# HHKBLite2BTforArduinoProMicro33.net
KiCad netlist of a schematic drawn in EAGLE
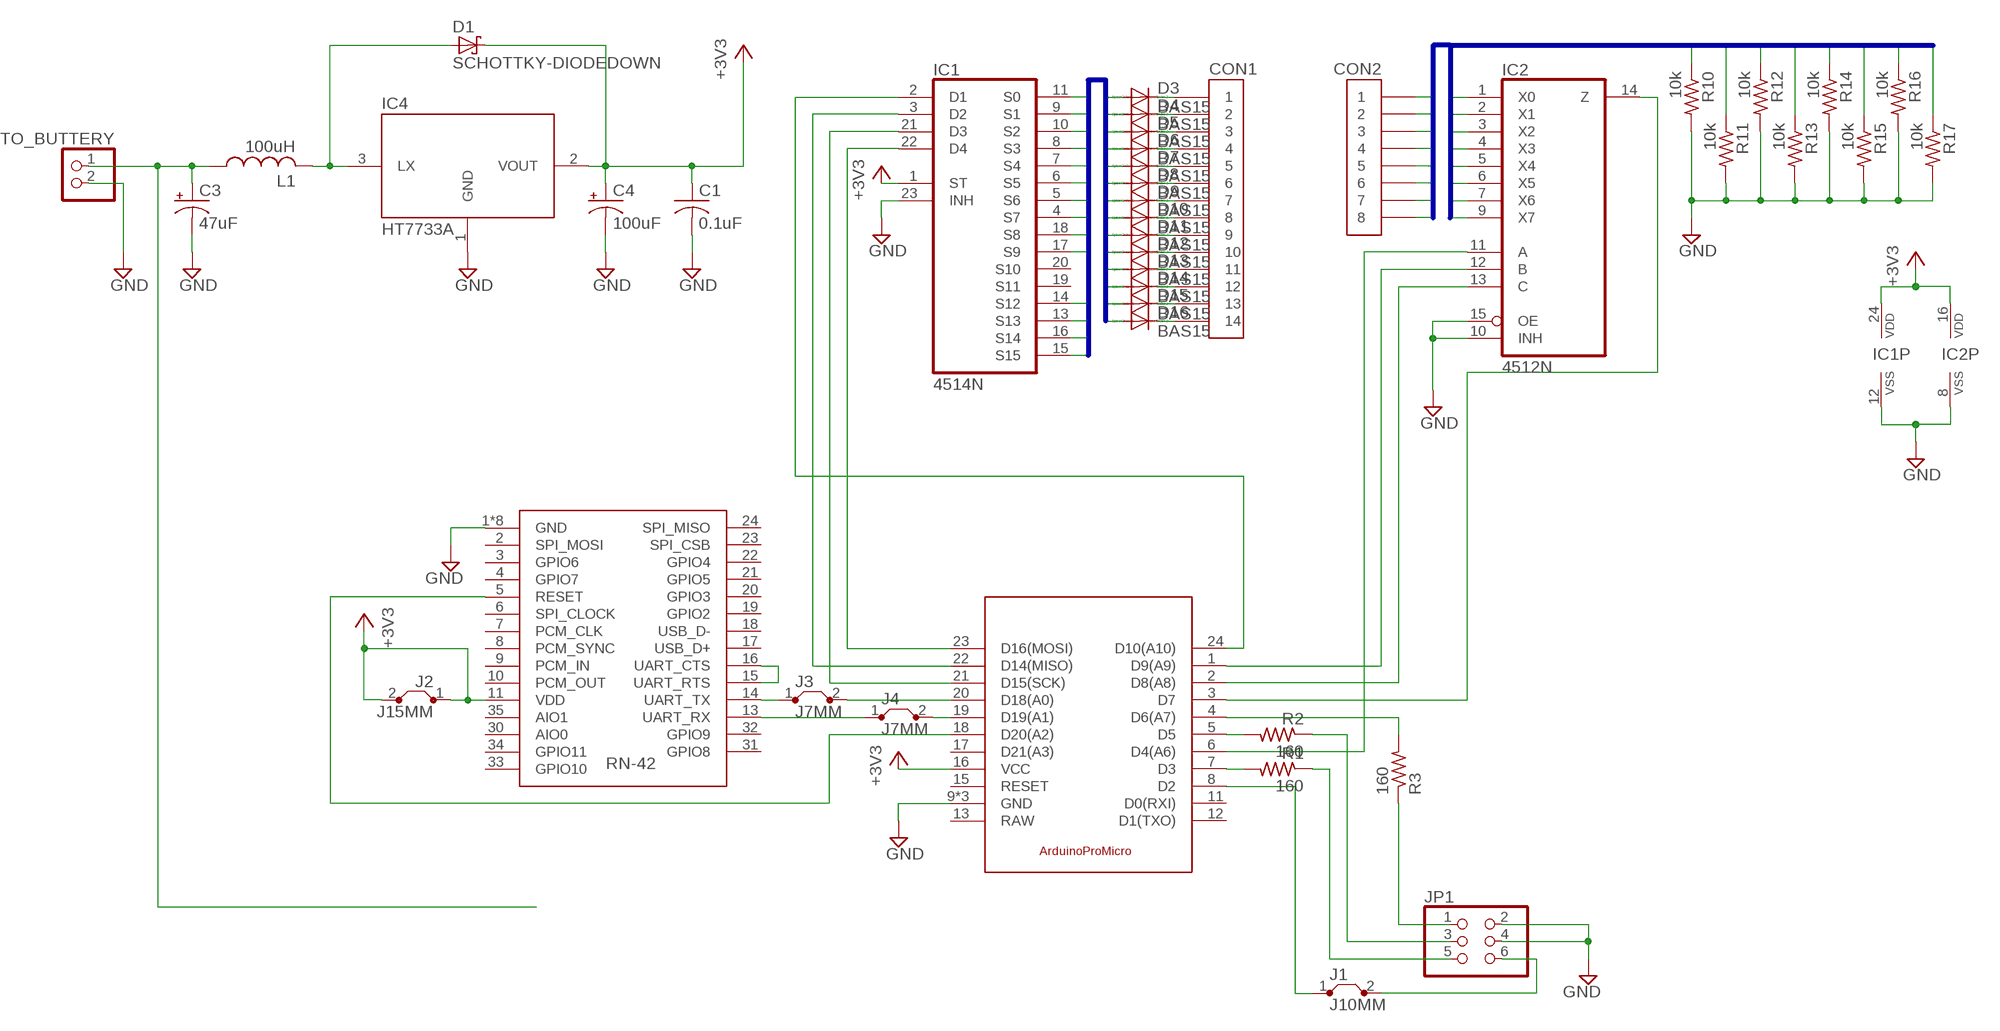
[diagram p0: schematic, sheet 1]

(export (version "E")
  (design (tool "Eeschema 10.0.6"))
  (components
    (comp (ref "C1")
      (value "0.1uF")
      (footprint "eagle-import:C050-024X044")
      (libsource (lib "eagle-import") (part "C-US050-024X044"))
    )
    (comp (ref "C3")
      (value "47uF")
      (footprint "eagle-import:E2,5-7")
      (libsource (lib "eagle-import") (part "CPOL-USE2.5-7"))
    )
    (comp (ref "C4")
      (value "100uF")
      (footprint "eagle-import:E2,5-7")
      (libsource (lib "eagle-import") (part "CPOL-USE2.5-7"))
    )
    (comp (ref "CON1")
      (value "45045-1445")
      (footprint "eagle-import:52045-1445")
      (libsource (lib "eagle-import") (part "45045-1445"))
    )
    (comp (ref "CON2")
      (value "45045-0845")
      (footprint "eagle-import:52045-0845")
      (libsource (lib "eagle-import") (part "45045-0845"))
    )
    (comp (ref "D1")
      (value "SCHOTTKY-DIODEDOWN")
      (footprint "eagle-import:DIODE-STAND-DOWN")
      (libsource (lib "eagle-import") (part "SCHOTTKY-DIODEDOWN"))
    )
    (comp (ref "D3")
      (value "BAS15")
      (footprint "eagle-import:DO34-7")
      (libsource (lib "eagle-import") (part "BAS15"))
    )
    (comp (ref "D4")
      (value "BAS15")
      (footprint "eagle-import:DO34-7")
      (libsource (lib "eagle-import") (part "BAS15"))
    )
    (comp (ref "D5")
      (value "BAS15")
      (footprint "eagle-import:DO34-7")
      (libsource (lib "eagle-import") (part "BAS15"))
    )
    (comp (ref "D6")
      (value "BAS15")
      (footprint "eagle-import:DO34-7")
      (libsource (lib "eagle-import") (part "BAS15"))
    )
    (comp (ref "D7")
      (value "BAS15")
      (footprint "eagle-import:DO34-7")
      (libsource (lib "eagle-import") (part "BAS15"))
    )
    (comp (ref "D8")
      (value "BAS15")
      (footprint "eagle-import:DO34-7")
      (libsource (lib "eagle-import") (part "BAS15"))
    )
    (comp (ref "D9")
      (value "BAS15")
      (footprint "eagle-import:DO34-7")
      (libsource (lib "eagle-import") (part "BAS15"))
    )
    (comp (ref "D10")
      (value "BAS15")
      (footprint "eagle-import:DO34-7")
      (libsource (lib "eagle-import") (part "BAS15"))
    )
    (comp (ref "D11")
      (value "BAS15")
      (footprint "eagle-import:DO34-7")
      (libsource (lib "eagle-import") (part "BAS15"))
    )
    (comp (ref "D12")
      (value "BAS15")
      (footprint "eagle-import:DO34-7")
      (libsource (lib "eagle-import") (part "BAS15"))
    )
    (comp (ref "D13")
      (value "BAS15")
      (footprint "eagle-import:DO34-7")
      (libsource (lib "eagle-import") (part "BAS15"))
    )
    (comp (ref "D14")
      (value "BAS15")
      (footprint "eagle-import:DO34-7")
      (libsource (lib "eagle-import") (part "BAS15"))
    )
    (comp (ref "D15")
      (value "BAS15")
      (footprint "eagle-import:DO34-7")
      (libsource (lib "eagle-import") (part "BAS15"))
    )
    (comp (ref "D16")
      (value "BAS15")
      (footprint "eagle-import:DO34-7")
      (libsource (lib "eagle-import") (part "BAS15"))
    )
    (comp (ref "IC1")
      (value "4514N")
      (footprint "eagle-import:DIL24-6")
      (libsource (lib "eagle-import") (part "4514N"))
    )
    (comp (ref "IC2")
      (value "4512N")
      (footprint "eagle-import:DIL16")
      (libsource (lib "eagle-import") (part "4512N"))
    )
    (comp (ref "IC4")
      (value "HT7733A")
      (footprint "eagle-import:TO-92")
      (libsource (lib "eagle-import") (part "HT7733A"))
    )
    (comp (ref "J1")
      (value "J10MM")
      (footprint "eagle-import:10")
      (libsource (lib "eagle-import") (part "J10MM"))
    )
    (comp (ref "J2")
      (value "J15MM")
      (footprint "eagle-import:15")
      (libsource (lib "eagle-import") (part "J15MM"))
    )
    (comp (ref "J3")
      (value "J7MM")
      (footprint "eagle-import:07")
      (libsource (lib "eagle-import") (part "J7MM"))
    )
    (comp (ref "J4")
      (value "J7MM")
      (footprint "eagle-import:07")
      (libsource (lib "eagle-import") (part "J7MM"))
    )
    (comp (ref "JP1")
      (value "PINHD-2X3/90")
      (footprint "eagle-import:2X03_90")
      (libsource (lib "eagle-import") (part "PINHD-2X3/90"))
    )
    (comp (ref "L1")
      (value "100uH")
      (footprint "eagle-import:E5-10")
      (libsource (lib "eagle-import") (part "LL5-10"))
    )
    (comp (ref "R1")
      (value "160")
      (footprint "eagle-import:0207_7")
      (libsource (lib "eagle-import") (part "R-US_0207/7"))
    )
    (comp (ref "R2")
      (value "160")
      (footprint "eagle-import:0207_7")
      (libsource (lib "eagle-import") (part "R-US_0207/7"))
    )
    (comp (ref "R3")
      (value "160")
      (footprint "eagle-import:0207_10")
      (libsource (lib "eagle-import") (part "R-US_0207/10"))
    )
    (comp (ref "R10")
      (value "10k")
      (footprint "eagle-import:0207_7")
      (libsource (lib "eagle-import") (part "R-US_0207/7"))
    )
    (comp (ref "R11")
      (value "10k")
      (footprint "eagle-import:0207_7")
      (libsource (lib "eagle-import") (part "R-US_0207/7"))
    )
    (comp (ref "R12")
      (value "10k")
      (footprint "eagle-import:0207_7")
      (libsource (lib "eagle-import") (part "R-US_0207/7"))
    )
    (comp (ref "R13")
      (value "10k")
      (footprint "eagle-import:0207_10")
      (libsource (lib "eagle-import") (part "resistor_R-US_0207/10"))
    )
    (comp (ref "R14")
      (value "10k")
      (footprint "eagle-import:0207_7")
      (libsource (lib "eagle-import") (part "R-US_0207/7"))
    )
    (comp (ref "R15")
      (value "10k")
      (footprint "eagle-import:0207_7")
      (libsource (lib "eagle-import") (part "R-US_0207/7"))
    )
    (comp (ref "R16")
      (value "10k")
      (footprint "eagle-import:0207_7")
      (libsource (lib "eagle-import") (part "R-US_0207/7"))
    )
    (comp (ref "R17")
      (value "10k")
      (footprint "eagle-import:0207_7")
      (libsource (lib "eagle-import") (part "R-US_0207/7"))
    )
    (comp (ref "TO_BUTTERY")
      (value "PINHD-1X2")
      (footprint "eagle-import:1X02")
      (libsource (lib "eagle-import") (part "PINHD-1X2"))
    )
    (comp (ref "U$1")
      (value "RN-42")
      (footprint "eagle-import:RN-42")
      (libsource (lib "eagle-import") (part "RN-42"))
    )
    (comp (ref "U$2")
      (value "ARDUINO_PRO_MICRO")
      (footprint "eagle-import:ARDUINO_PRO_MICRO")
      (libsource (lib "eagle-import") (part "ARDUINO_PRO_MICRO"))
    )
  )
  (nets
    (net (code "1") (name "+3V3") (class "Default")
      (node (ref "C1") (pin "1") (pinfunction "1_1") (pintype "passive"))
      (node (ref "C4") (pin "+") (pinfunction "+_+") (pintype "passive"))
      (node (ref "D1") (pin "C") (pinfunction "C_C") (pintype "passive"))
      (node (ref "IC1") (pin "1") (pinfunction "ST_1") (pintype "input"))
      (node (ref "IC1") (pin "24") (pinfunction "VDD_24") (pintype "power_in"))
      (node (ref "IC2") (pin "16") (pinfunction "VDD_16") (pintype "power_in"))
      (node (ref "IC4") (pin "2") (pinfunction "VOUT_2") (pintype "output"))
      (node (ref "J2") (pin "1") (pinfunction "1_1") (pintype "passive"))
      (node (ref "J2") (pin "2") (pinfunction "2_2") (pintype "passive"))
      (node (ref "U$1") (pin "11") (pinfunction "VDD_11") (pintype "power_in"))
      (node (ref "U$2") (pin "16") (pinfunction "VCC_16") (pintype "power_in"))
    )
    (net (code "2") (name "/CON1BUS_O0") (class "Default")
      (node (ref "D3") (pin "A") (pinfunction "A_A") (pintype "passive"))
      (node (ref "IC1") (pin "11") (pinfunction "S0_11") (pintype "output"))
    )
    (net (code "3") (name "/CON1BUS_O1") (class "Default")
      (node (ref "D5") (pin "A") (pinfunction "A_A") (pintype "passive"))
      (node (ref "IC1") (pin "9") (pinfunction "S1_9") (pintype "output"))
    )
    (net (code "4") (name "/CON1BUS_O2") (class "Default")
      (node (ref "D4") (pin "A") (pinfunction "A_A") (pintype "passive"))
      (node (ref "IC1") (pin "10") (pinfunction "S2_10") (pintype "output"))
    )
    (net (code "5") (name "/CON1BUS_O3") (class "Default")
      (node (ref "D6") (pin "A") (pinfunction "A_A") (pintype "passive"))
      (node (ref "IC1") (pin "8") (pinfunction "S3_8") (pintype "output"))
    )
    (net (code "6") (name "/CON1BUS_O4") (class "Default")
      (node (ref "D7") (pin "A") (pinfunction "A_A") (pintype "passive"))
      (node (ref "IC1") (pin "7") (pinfunction "S4_7") (pintype "output"))
    )
    (net (code "7") (name "/CON1BUS_O5") (class "Default")
      (node (ref "D8") (pin "A") (pinfunction "A_A") (pintype "passive"))
      (node (ref "IC1") (pin "6") (pinfunction "S5_6") (pintype "output"))
    )
    (net (code "8") (name "/CON1BUS_O6") (class "Default")
      (node (ref "D9") (pin "A") (pinfunction "A_A") (pintype "passive"))
      (node (ref "IC1") (pin "5") (pinfunction "S6_5") (pintype "output"))
    )
    (net (code "9") (name "/CON1BUS_O7") (class "Default")
      (node (ref "D10") (pin "A") (pinfunction "A_A") (pintype "passive"))
      (node (ref "IC1") (pin "4") (pinfunction "S7_4") (pintype "output"))
    )
    (net (code "10") (name "/CON1BUS_O8") (class "Default")
      (node (ref "D11") (pin "A") (pinfunction "A_A") (pintype "passive"))
      (node (ref "IC1") (pin "18") (pinfunction "S8_18") (pintype "output"))
    )
    (net (code "11") (name "/CON1BUS_O9") (class "Default")
      (node (ref "D16") (pin "A") (pinfunction "A_A") (pintype "passive"))
      (node (ref "IC1") (pin "17") (pinfunction "S9_17") (pintype "output"))
    )
    (net (code "12") (name "/CON1BUS_O12") (class "Default")
      (node (ref "D13") (pin "A") (pinfunction "A_A") (pintype "passive"))
      (node (ref "IC1") (pin "14") (pinfunction "S12_14") (pintype "output"))
    )
    (net (code "13") (name "/CON1BUS_O13") (class "Default")
      (node (ref "D12") (pin "A") (pinfunction "A_A") (pintype "passive"))
      (node (ref "IC1") (pin "13") (pinfunction "S13_13") (pintype "output"))
    )
    (net (code "14") (name "/CON1BUS_O14") (class "Default")
      (node (ref "D15") (pin "A") (pinfunction "A_A") (pintype "passive"))
      (node (ref "IC1") (pin "16") (pinfunction "S14_16") (pintype "output"))
    )
    (net (code "15") (name "/CON1BUS_O15") (class "Default")
      (node (ref "D14") (pin "A") (pinfunction "A_A") (pintype "passive"))
      (node (ref "IC1") (pin "15") (pinfunction "S15_15") (pintype "output"))
    )
    (net (code "16") (name "/CON2BUS_D0") (class "Default")
      (node (ref "CON2") (pin "8") (pinfunction "8_8") (pintype "bidirectional"))
      (node (ref "IC2") (pin "1") (pinfunction "X0_1") (pintype "input"))
      (node (ref "R10") (pin "1") (pinfunction "1_1") (pintype "passive"))
    )
    (net (code "17") (name "/CON2BUS_D1") (class "Default")
      (node (ref "CON2") (pin "7") (pinfunction "7_7") (pintype "bidirectional"))
      (node (ref "IC2") (pin "2") (pinfunction "X1_2") (pintype "input"))
      (node (ref "R11") (pin "1") (pinfunction "1_1") (pintype "passive"))
    )
    (net (code "18") (name "/CON2BUS_D2") (class "Default")
      (node (ref "CON2") (pin "6") (pinfunction "6_6") (pintype "bidirectional"))
      (node (ref "IC2") (pin "3") (pinfunction "X2_3") (pintype "input"))
      (node (ref "R12") (pin "1") (pinfunction "1_1") (pintype "passive"))
    )
    (net (code "19") (name "/CON2BUS_D3") (class "Default")
      (node (ref "CON2") (pin "5") (pinfunction "5_5") (pintype "bidirectional"))
      (node (ref "IC2") (pin "4") (pinfunction "X3_4") (pintype "input"))
      (node (ref "R13") (pin "1") (pinfunction "1_1") (pintype "passive"))
    )
    (net (code "20") (name "/CON2BUS_D4") (class "Default")
      (node (ref "CON2") (pin "4") (pinfunction "4_4") (pintype "bidirectional"))
      (node (ref "IC2") (pin "5") (pinfunction "X4_5") (pintype "input"))
      (node (ref "R14") (pin "1") (pinfunction "1_1") (pintype "passive"))
    )
    (net (code "21") (name "/CON2BUS_D5") (class "Default")
      (node (ref "CON2") (pin "3") (pinfunction "3_3") (pintype "bidirectional"))
      (node (ref "IC2") (pin "6") (pinfunction "X5_6") (pintype "input"))
      (node (ref "R15") (pin "1") (pinfunction "1_1") (pintype "passive"))
    )
    (net (code "22") (name "/CON2BUS_D6") (class "Default")
      (node (ref "CON2") (pin "2") (pinfunction "2_2") (pintype "bidirectional"))
      (node (ref "IC2") (pin "7") (pinfunction "X6_7") (pintype "input"))
      (node (ref "R16") (pin "1") (pinfunction "1_1") (pintype "passive"))
    )
    (net (code "23") (name "/CON2BUS_D7") (class "Default")
      (node (ref "CON2") (pin "1") (pinfunction "1_1") (pintype "bidirectional"))
      (node (ref "IC2") (pin "9") (pinfunction "X7_9") (pintype "input"))
      (node (ref "R17") (pin "1") (pinfunction "1_1") (pintype "passive"))
    )
    (net (code "24") (name "/RAW") (class "Default")
      (node (ref "U$2") (pin "13") (pinfunction "RAW_13") (pintype "power_in"))
    )
    (net (code "25") (name "GND") (class "Default")
      (node (ref "C1") (pin "2") (pinfunction "2_2") (pintype "passive"))
      (node (ref "C3") (pin "-") (pinfunction "-_-") (pintype "passive"))
      (node (ref "C4") (pin "-") (pinfunction "-_-") (pintype "passive"))
      (node (ref "IC1") (pin "12") (pinfunction "VSS_12") (pintype "power_in"))
      (node (ref "IC1") (pin "23") (pinfunction "INH_23") (pintype "input"))
      (node (ref "IC2") (pin "10") (pinfunction "INH_10") (pintype "input"))
      (node (ref "IC2") (pin "15") (pinfunction "OE_15") (pintype "input"))
      (node (ref "IC2") (pin "8") (pinfunction "VSS_8") (pintype "power_in"))
      (node (ref "IC4") (pin "1") (pinfunction "GND_1") (pintype "power_in"))
      (node (ref "JP1") (pin "2") (pinfunction "2_2") (pintype "passive"))
      (node (ref "JP1") (pin "4") (pinfunction "4_4") (pintype "passive"))
      (node (ref "R10") (pin "2") (pinfunction "2_2") (pintype "passive"))
      (node (ref "R11") (pin "2") (pinfunction "2_2") (pintype "passive"))
      (node (ref "R12") (pin "2") (pinfunction "2_2") (pintype "passive"))
      (node (ref "R13") (pin "2") (pinfunction "2_2") (pintype "passive"))
      (node (ref "R14") (pin "2") (pinfunction "2_2") (pintype "passive"))
      (node (ref "R15") (pin "2") (pinfunction "2_2") (pintype "passive"))
      (node (ref "R16") (pin "2") (pinfunction "2_2") (pintype "passive"))
      (node (ref "R17") (pin "2") (pinfunction "2_2") (pintype "passive"))
      (node (ref "TO_BUTTERY") (pin "2") (pinfunction "2_2") (pintype "passive"))
      (node (ref "U$1") (pin "1") (pinfunction "GND_1") (pintype "power_in"))
      (node (ref "U$1") (pin "12") (pinfunction "GND_12") (pintype "power_in"))
      (node (ref "U$1") (pin "28") (pinfunction "GND_28") (pintype "power_in"))
      (node (ref "U$1") (pin "29") (pinfunction "GND_29") (pintype "power_in"))
      (node (ref "U$1") (pin "GND1") (pinfunction "GND_GND1") (pintype "power_in"))
      (node (ref "U$1") (pin "GND2") (pinfunction "GND_GND2") (pintype "power_in"))
      (node (ref "U$1") (pin "GND3") (pinfunction "GND_GND3") (pintype "power_in"))
      (node (ref "U$1") (pin "GND4") (pinfunction "GND_GND4") (pintype "power_in"))
      (node (ref "U$2") (pin "10") (pinfunction "GND_10") (pintype "power_in"))
      (node (ref "U$2") (pin "14") (pinfunction "GND_14") (pintype "power_in"))
      (node (ref "U$2") (pin "9") (pinfunction "GND_9") (pintype "power_in"))
    )
    (net (code "26") (name "Net-(CON1-Pad1)") (class "Default")
      (node (ref "CON1") (pin "1") (pinfunction "1_1") (pintype "bidirectional"))
      (node (ref "D3") (pin "C") (pinfunction "C_C") (pintype "passive"))
    )
    (net (code "27") (name "Net-(CON1-Pad2)") (class "Default")
      (node (ref "CON1") (pin "2") (pinfunction "2_2") (pintype "bidirectional"))
      (node (ref "D4") (pin "C") (pinfunction "C_C") (pintype "passive"))
    )
    (net (code "28") (name "Net-(CON1-Pad3)") (class "Default")
      (node (ref "CON1") (pin "3") (pinfunction "3_3") (pintype "bidirectional"))
      (node (ref "D5") (pin "C") (pinfunction "C_C") (pintype "passive"))
    )
    (net (code "29") (name "Net-(CON1-Pad4)") (class "Default")
      (node (ref "CON1") (pin "4") (pinfunction "4_4") (pintype "bidirectional"))
      (node (ref "D6") (pin "C") (pinfunction "C_C") (pintype "passive"))
    )
    (net (code "30") (name "Net-(CON1-Pad5)") (class "Default")
      (node (ref "CON1") (pin "5") (pinfunction "5_5") (pintype "bidirectional"))
      (node (ref "D7") (pin "C") (pinfunction "C_C") (pintype "passive"))
    )
    (net (code "31") (name "Net-(CON1-Pad6)") (class "Default")
      (node (ref "CON1") (pin "6") (pinfunction "6_6") (pintype "bidirectional"))
      (node (ref "D8") (pin "C") (pinfunction "C_C") (pintype "passive"))
    )
    (net (code "32") (name "Net-(CON1-Pad7)") (class "Default")
      (node (ref "CON1") (pin "7") (pinfunction "7_7") (pintype "bidirectional"))
      (node (ref "D9") (pin "C") (pinfunction "C_C") (pintype "passive"))
    )
    (net (code "33") (name "Net-(CON1-Pad8)") (class "Default")
      (node (ref "CON1") (pin "8") (pinfunction "8_8") (pintype "bidirectional"))
      (node (ref "D10") (pin "C") (pinfunction "C_C") (pintype "passive"))
    )
    (net (code "34") (name "Net-(CON1-Pad9)") (class "Default")
      (node (ref "CON1") (pin "9") (pinfunction "9_9") (pintype "bidirectional"))
      (node (ref "D11") (pin "C") (pinfunction "C_C") (pintype "passive"))
    )
    (net (code "35") (name "Net-(CON1-Pad10)") (class "Default")
      (node (ref "CON1") (pin "10") (pinfunction "10_10") (pintype "bidirectional"))
      (node (ref "D12") (pin "C") (pinfunction "C_C") (pintype "passive"))
    )
    (net (code "36") (name "Net-(CON1-Pad11)") (class "Default")
      (node (ref "CON1") (pin "11") (pinfunction "11_11") (pintype "bidirectional"))
      (node (ref "D13") (pin "C") (pinfunction "C_C") (pintype "passive"))
    )
    (net (code "37") (name "Net-(CON1-Pad12)") (class "Default")
      (node (ref "CON1") (pin "12") (pinfunction "12_12") (pintype "bidirectional"))
      (node (ref "D14") (pin "C") (pinfunction "C_C") (pintype "passive"))
    )
    (net (code "38") (name "Net-(CON1-Pad13)") (class "Default")
      (node (ref "CON1") (pin "13") (pinfunction "13_13") (pintype "bidirectional"))
      (node (ref "D15") (pin "C") (pinfunction "C_C") (pintype "passive"))
    )
    (net (code "39") (name "Net-(CON1-Pad14)") (class "Default")
      (node (ref "CON1") (pin "14") (pinfunction "14_14") (pintype "bidirectional"))
      (node (ref "D16") (pin "C") (pinfunction "C_C") (pintype "passive"))
    )
    (net (code "40") (name "Net-(IC1A-D1)") (class "Default")
      (node (ref "IC1") (pin "2") (pinfunction "D1_2") (pintype "input"))
      (node (ref "U$2") (pin "24") (pinfunction "D10(A10)_24") (pintype "bidirectional"))
    )
    (net (code "41") (name "Net-(IC1A-D2)") (class "Default")
      (node (ref "IC1") (pin "3") (pinfunction "D2_3") (pintype "input"))
      (node (ref "U$2") (pin "22") (pinfunction "D14(MISO)_22") (pintype "bidirectional"))
    )
    (net (code "42") (name "Net-(IC1A-D3)") (class "Default")
      (node (ref "IC1") (pin "21") (pinfunction "D3_21") (pintype "input"))
      (node (ref "U$2") (pin "21") (pinfunction "D15(SCK)_21") (pintype "bidirectional"))
    )
    (net (code "43") (name "Net-(IC1A-D4)") (class "Default")
      (node (ref "IC1") (pin "22") (pinfunction "D4_22") (pintype "input"))
      (node (ref "U$2") (pin "23") (pinfunction "D16(MOSI)_23") (pintype "bidirectional"))
    )
    (net (code "44") (name "Net-(IC2A-A)") (class "Default")
      (node (ref "IC2") (pin "11") (pinfunction "A_11") (pintype "input"))
      (node (ref "U$2") (pin "6") (pinfunction "D4(A6)_6") (pintype "bidirectional"))
    )
    (net (code "45") (name "Net-(IC2A-B)") (class "Default")
      (node (ref "IC2") (pin "12") (pinfunction "B_12") (pintype "input"))
      (node (ref "U$2") (pin "1") (pinfunction "D9(A9)_1") (pintype "bidirectional"))
    )
    (net (code "46") (name "Net-(IC2A-C)") (class "Default")
      (node (ref "IC2") (pin "13") (pinfunction "C_13") (pintype "input"))
      (node (ref "U$2") (pin "2") (pinfunction "D8(A8)_2") (pintype "bidirectional"))
    )
    (net (code "47") (name "Net-(IC2A-Z)") (class "Default")
      (node (ref "IC2") (pin "14") (pinfunction "Z_14") (pintype "tri_state"))
      (node (ref "U$2") (pin "3") (pinfunction "D7_3") (pintype "bidirectional"))
    )
    (net (code "48") (name "Net-(IC4-LX)") (class "Default")
      (node (ref "D1") (pin "A") (pinfunction "A_A") (pintype "passive"))
      (node (ref "IC4") (pin "3") (pinfunction "LX_3") (pintype "input"))
      (node (ref "L1") (pin "+1") (pinfunction "2_+1") (pintype "passive"))
    )
    (net (code "49") (name "Net-(J1-Pad2)") (class "Default")
      (node (ref "J1") (pin "2") (pinfunction "2_2") (pintype "passive"))
      (node (ref "JP1") (pin "6") (pinfunction "6_6") (pintype "passive"))
    )
    (net (code "50") (name "Net-(JP1-Pad1)") (class "Default")
      (node (ref "JP1") (pin "1") (pinfunction "1_1") (pintype "passive"))
      (node (ref "R3") (pin "1") (pinfunction "1_1") (pintype "passive"))
    )
    (net (code "51") (name "Net-(JP1-Pad3)") (class "Default")
      (node (ref "JP1") (pin "3") (pinfunction "3_3") (pintype "passive"))
      (node (ref "R2") (pin "1") (pinfunction "1_1") (pintype "passive"))
    )
    (net (code "52") (name "Net-(JP1-Pad5)") (class "Default")
      (node (ref "JP1") (pin "5") (pinfunction "5_5") (pintype "passive"))
      (node (ref "R1") (pin "1") (pinfunction "1_1") (pintype "passive"))
    )
    (net (code "53") (name "Net-(L1-1)") (class "Default")
      (node (ref "C3") (pin "+") (pinfunction "+_+") (pintype "passive"))
      (node (ref "L1") (pin "+") (pinfunction "1_+") (pintype "passive"))
      (node (ref "TO_BUTTERY") (pin "1") (pinfunction "1_1") (pintype "passive"))
    )
    (net (code "54") (name "Net-(U$1-RESET)") (class "Default")
      (node (ref "U$1") (pin "5") (pinfunction "RESET_5") (pintype "bidirectional"))
      (node (ref "U$2") (pin "18") (pinfunction "D20(A2)_18") (pintype "bidirectional"))
    )
    (net (code "55") (name "Net-(U$1-UART_CTS)") (class "Default")
      (node (ref "U$1") (pin "15") (pinfunction "UART_RTS_15") (pintype "bidirectional"))
      (node (ref "U$1") (pin "16") (pinfunction "UART_CTS_16") (pintype "bidirectional"))
    )
    (net (code "56") (name "Net-(U$1-UART_RX)") (class "Default")
      (node (ref "J4") (pin "1") (pinfunction "1_1") (pintype "passive"))
      (node (ref "U$1") (pin "13") (pinfunction "UART_RX_13") (pintype "bidirectional"))
    )
    (net (code "57") (name "Net-(U$1-UART_TX)") (class "Default")
      (node (ref "J3") (pin "1") (pinfunction "1_1") (pintype "passive"))
      (node (ref "U$1") (pin "14") (pinfunction "UART_TX_14") (pintype "bidirectional"))
    )
    (net (code "58") (name "Net-(U$2-D2)") (class "Default")
      (node (ref "J1") (pin "1") (pinfunction "1_1") (pintype "passive"))
      (node (ref "U$2") (pin "8") (pinfunction "D2_8") (pintype "bidirectional"))
    )
    (net (code "59") (name "Net-(U$2-D3)") (class "Default")
      (node (ref "R1") (pin "2") (pinfunction "2_2") (pintype "passive"))
      (node (ref "U$2") (pin "7") (pinfunction "D3_7") (pintype "bidirectional"))
    )
    (net (code "60") (name "Net-(U$2-D5)") (class "Default")
      (node (ref "R2") (pin "2") (pinfunction "2_2") (pintype "passive"))
      (node (ref "U$2") (pin "5") (pinfunction "D5_5") (pintype "bidirectional"))
    )
    (net (code "61") (name "Net-(U$2-D6(A7))") (class "Default")
      (node (ref "R3") (pin "2") (pinfunction "2_2") (pintype "passive"))
      (node (ref "U$2") (pin "4") (pinfunction "D6(A7)_4") (pintype "bidirectional"))
    )
    (net (code "62") (name "Net-(U$2-D18(A0))") (class "Default")
      (node (ref "J3") (pin "2") (pinfunction "2_2") (pintype "passive"))
      (node (ref "U$2") (pin "20") (pinfunction "D18(A0)_20") (pintype "bidirectional"))
    )
    (net (code "63") (name "Net-(U$2-D19(A1))") (class "Default")
      (node (ref "J4") (pin "2") (pinfunction "2_2") (pintype "passive"))
      (node (ref "U$2") (pin "19") (pinfunction "D19(A1)_19") (pintype "bidirectional"))
    )
    (net (code "64") (name "unconnected-(IC1A-S10-Pad20)") (class "Default")
      (node (ref "IC1") (pin "20") (pinfunction "S10_20") (pintype "output"))
    )
    (net (code "65") (name "unconnected-(IC1A-S11-Pad19)") (class "Default")
      (node (ref "IC1") (pin "19") (pinfunction "S11_19") (pintype "output"))
    )
    (net (code "66") (name "unconnected-(U$1-AIO0-Pad30)") (class "Default")
      (node (ref "U$1") (pin "30") (pinfunction "AIO0_30") (pintype "bidirectional"))
    )
    (net (code "67") (name "unconnected-(U$1-AIO1-Pad35)") (class "Default")
      (node (ref "U$1") (pin "35") (pinfunction "AIO1_35") (pintype "bidirectional"))
    )
    (net (code "68") (name "unconnected-(U$1-GPIO2-Pad19)") (class "Default")
      (node (ref "U$1") (pin "19") (pinfunction "GPIO2_19") (pintype "bidirectional"))
    )
    (net (code "69") (name "unconnected-(U$1-GPIO3-Pad20)") (class "Default")
      (node (ref "U$1") (pin "20") (pinfunction "GPIO3_20") (pintype "bidirectional"))
    )
    (net (code "70") (name "unconnected-(U$1-GPIO4-Pad22)") (class "Default")
      (node (ref "U$1") (pin "22") (pinfunction "GPIO4_22") (pintype "bidirectional"))
    )
    (net (code "71") (name "unconnected-(U$1-GPIO5-Pad21)") (class "Default")
      (node (ref "U$1") (pin "21") (pinfunction "GPIO5_21") (pintype "bidirectional"))
    )
    (net (code "72") (name "unconnected-(U$1-GPIO6-Pad3)") (class "Default")
      (node (ref "U$1") (pin "3") (pinfunction "GPIO6_3") (pintype "bidirectional"))
    )
    (net (code "73") (name "unconnected-(U$1-GPIO7-Pad4)") (class "Default")
      (node (ref "U$1") (pin "4") (pinfunction "GPIO7_4") (pintype "bidirectional"))
    )
    (net (code "74") (name "unconnected-(U$1-GPIO8-Pad31)") (class "Default")
      (node (ref "U$1") (pin "31") (pinfunction "GPIO8_31") (pintype "bidirectional"))
    )
    (net (code "75") (name "unconnected-(U$1-GPIO9-Pad32)") (class "Default")
      (node (ref "U$1") (pin "32") (pinfunction "GPIO9_32") (pintype "bidirectional"))
    )
    (net (code "76") (name "unconnected-(U$1-GPIO10-Pad33)") (class "Default")
      (node (ref "U$1") (pin "33") (pinfunction "GPIO10_33") (pintype "bidirectional"))
    )
    (net (code "77") (name "unconnected-(U$1-GPIO11-Pad34)") (class "Default")
      (node (ref "U$1") (pin "34") (pinfunction "GPIO11_34") (pintype "bidirectional"))
    )
    (net (code "78") (name "unconnected-(U$1-PCM_CLK-Pad7)") (class "Default")
      (node (ref "U$1") (pin "7") (pinfunction "PCM_CLK_7") (pintype "bidirectional"))
    )
    (net (code "79") (name "unconnected-(U$1-PCM_IN-Pad9)") (class "Default")
      (node (ref "U$1") (pin "9") (pinfunction "PCM_IN_9") (pintype "bidirectional"))
    )
    (net (code "80") (name "unconnected-(U$1-PCM_OUT-Pad10)") (class "Default")
      (node (ref "U$1") (pin "10") (pinfunction "PCM_OUT_10") (pintype "bidirectional"))
    )
    (net (code "81") (name "unconnected-(U$1-PCM_SYNC-Pad8)") (class "Default")
      (node (ref "U$1") (pin "8") (pinfunction "PCM_SYNC_8") (pintype "bidirectional"))
    )
    (net (code "82") (name "unconnected-(U$1-SPI_CLOCK-Pad6)") (class "Default")
      (node (ref "U$1") (pin "6") (pinfunction "SPI_CLOCK_6") (pintype "bidirectional"))
    )
    (net (code "83") (name "unconnected-(U$1-SPI_CSB-Pad23)") (class "Default")
      (node (ref "U$1") (pin "23") (pinfunction "SPI_CSB_23") (pintype "bidirectional"))
    )
    (net (code "84") (name "unconnected-(U$1-SPI_MISO-Pad24)") (class "Default")
      (node (ref "U$1") (pin "24") (pinfunction "SPI_MISO_24") (pintype "bidirectional"))
    )
    (net (code "85") (name "unconnected-(U$1-SPI_MOSI-Pad2)") (class "Default")
      (node (ref "U$1") (pin "2") (pinfunction "SPI_MOSI_2") (pintype "bidirectional"))
    )
    (net (code "86") (name "unconnected-(U$1-USB_D+-Pad17)") (class "Default")
      (node (ref "U$1") (pin "17") (pinfunction "USB_D+_17") (pintype "bidirectional"))
    )
    (net (code "87") (name "unconnected-(U$1-USB_D--Pad18)") (class "Default")
      (node (ref "U$1") (pin "18") (pinfunction "USB_D-_18") (pintype "bidirectional"))
    )
    (net (code "88") (name "unconnected-(U$2-D0(RXI)-Pad11)") (class "Default")
      (node (ref "U$2") (pin "11") (pinfunction "D0(RXI)_11") (pintype "bidirectional"))
    )
    (net (code "89") (name "unconnected-(U$2-D1(TXO)-Pad12)") (class "Default")
      (node (ref "U$2") (pin "12") (pinfunction "D1(TXO)_12") (pintype "bidirectional"))
    )
    (net (code "90") (name "unconnected-(U$2-D21(A3)-Pad17)") (class "Default")
      (node (ref "U$2") (pin "17") (pinfunction "D21(A3)_17") (pintype "bidirectional"))
    )
    (net (code "91") (name "unconnected-(U$2-RESET-Pad15)") (class "Default")
      (node (ref "U$2") (pin "15") (pinfunction "RESET_15") (pintype "bidirectional"))
    )
  )
)
